# ROB_V1_1.net
KiCad netlist of a schematic drawn in EAGLE
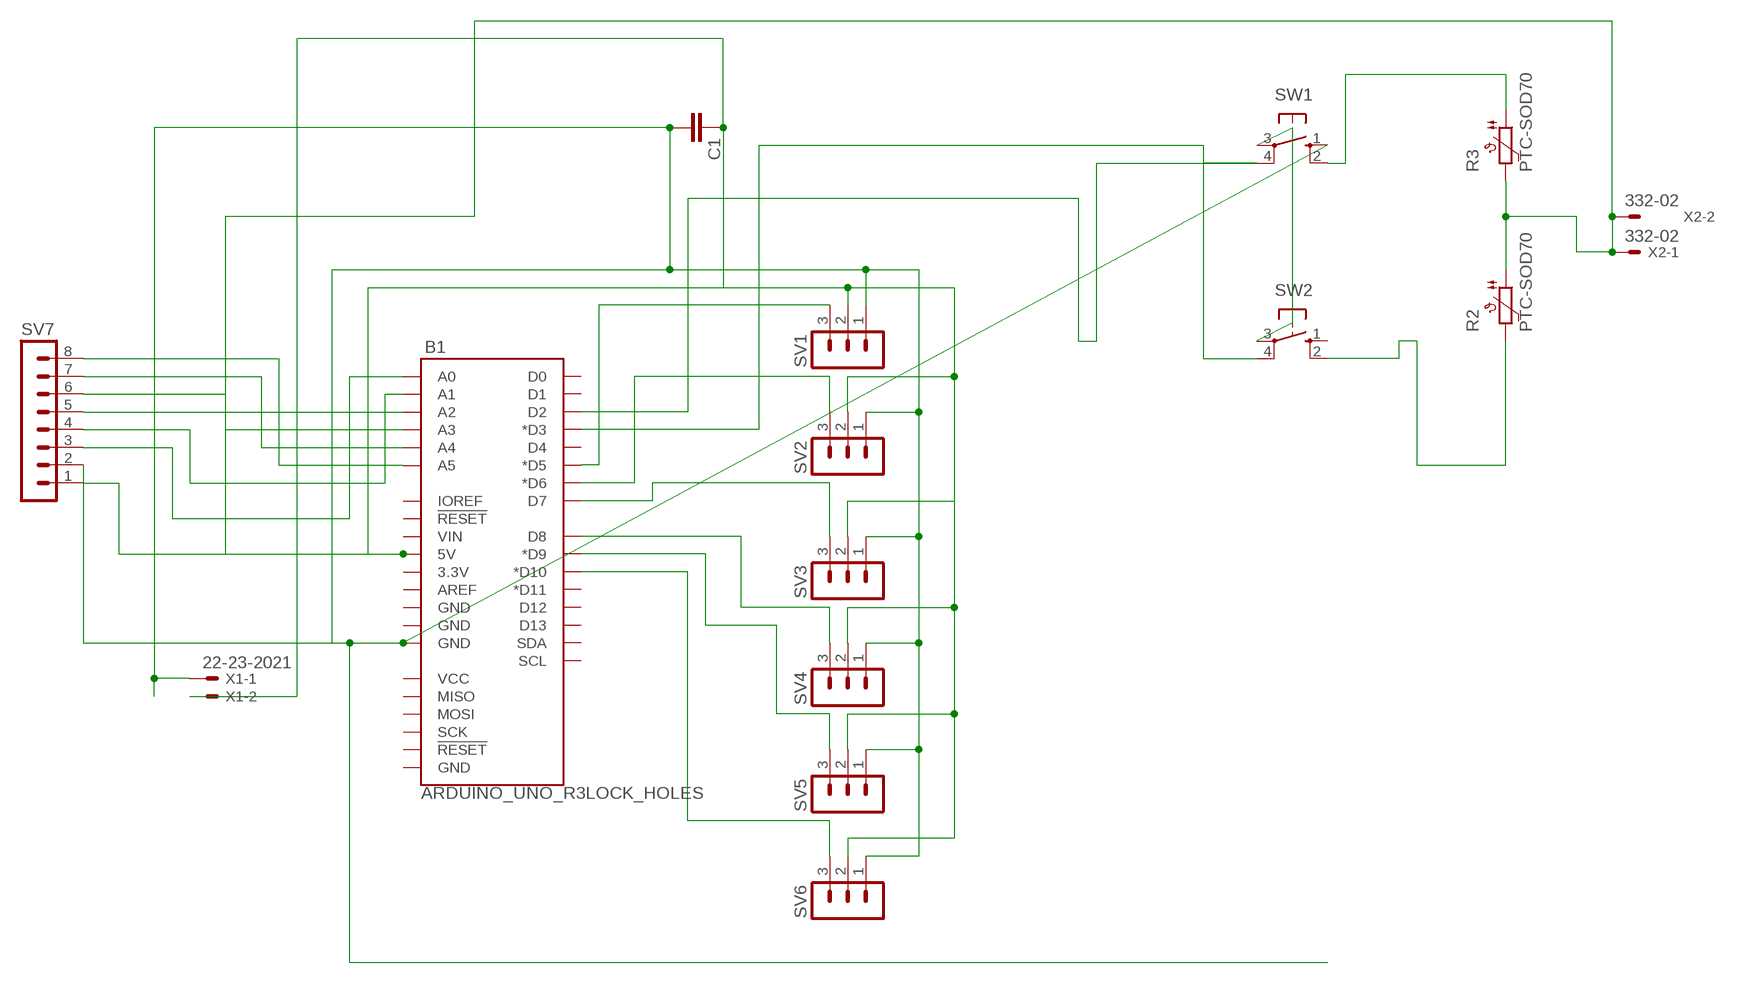
[diagram p0: schematic, sheet 1]

(export (version "E")
  (design (tool "Eeschema 10.0.6"))
  (components
    (comp (ref "B1")
      (value "ARDUINO_UNO_R3LOCK_HOLES")
      (footprint "eagle-import:ARDUINO_R3_LOCK_HOLES")
      (libsource (lib "eagle-import") (part "ARDUINO_UNO_R3LOCK_HOLES"))
    )
    (comp (ref "C1")
      (value "C2.5/2")
      (footprint "eagle-import:C2.5-2")
      (libsource (lib "eagle-import") (part "C2.5/2"))
    )
    (comp (ref "R2")
      (value "PTC-SOD70")
      (footprint "eagle-import:SOD70")
      (libsource (lib "eagle-import") (part "PTC-SOD70"))
    )
    (comp (ref "R3")
      (value "PTC-SOD70")
      (footprint "eagle-import:SOD70")
      (libsource (lib "eagle-import") (part "PTC-SOD70"))
    )
    (comp (ref "SV1")
      (value "MA03-1")
      (footprint "eagle-import:MA03-1")
      (libsource (lib "eagle-import") (part "MA03-1"))
    )
    (comp (ref "SV2")
      (value "MA03-1")
      (footprint "eagle-import:MA03-1")
      (libsource (lib "eagle-import") (part "MA03-1"))
    )
    (comp (ref "SV3")
      (value "MA03-1")
      (footprint "eagle-import:MA03-1")
      (libsource (lib "eagle-import") (part "MA03-1"))
    )
    (comp (ref "SV4")
      (value "MA03-1")
      (footprint "eagle-import:MA03-1")
      (libsource (lib "eagle-import") (part "MA03-1"))
    )
    (comp (ref "SV5")
      (value "MA03-1")
      (footprint "eagle-import:MA03-1")
      (libsource (lib "eagle-import") (part "MA03-1"))
    )
    (comp (ref "SV6")
      (value "MA03-1")
      (footprint "eagle-import:MA03-1")
      (libsource (lib "eagle-import") (part "MA03-1"))
    )
    (comp (ref "SV7")
      (value "MA08-1")
      (footprint "eagle-import:MA08-1")
      (libsource (lib "eagle-import") (part "MA08-1"))
    )
    (comp (ref "SW1")
      (value "10-XX")
      (footprint "eagle-import:B3F-10XX")
      (libsource (lib "eagle-import") (part "10-XX"))
    )
    (comp (ref "SW2")
      (value "10-XX")
      (footprint "eagle-import:B3F-10XX")
      (libsource (lib "eagle-import") (part "10-XX"))
    )
    (comp (ref "X1")
      (value "22-23-2021")
      (footprint "eagle-import:22-23-2021")
      (fields (field (name "MF") "MOLEX"))
      (libsource (lib "eagle-import") (part "22-23-2021"))
    )
    (comp (ref "X2")
      (value "332-02")
      (footprint "eagle-import:332-02")
      (libsource (lib "eagle-import") (part "332-02"))
    )
  )
  (nets
    (net (code "1") (name "Net-(B1-*D3)") (class "Default")
      (node (ref "B1") (pin "D3") (pinfunction "*D3_D3") (pintype "bidirectional"))
      (node (ref "SW2") (pin "4") (pinfunction "P1_4") (pintype "passive"))
    )
    (net (code "2") (name "Net-(B1-*D5)") (class "Default")
      (node (ref "B1") (pin "D5") (pinfunction "*D5_D5") (pintype "bidirectional"))
      (node (ref "SV1") (pin "3") (pinfunction "3_3") (pintype "passive"))
    )
    (net (code "3") (name "Net-(B1-*D6)") (class "Default")
      (node (ref "B1") (pin "D6") (pinfunction "*D6_D6") (pintype "bidirectional"))
      (node (ref "SV2") (pin "3") (pinfunction "3_3") (pintype "passive"))
    )
    (net (code "4") (name "Net-(B1-*D9)") (class "Default")
      (node (ref "B1") (pin "D9") (pinfunction "*D9_D9") (pintype "bidirectional"))
      (node (ref "SV5") (pin "3") (pinfunction "3_3") (pintype "passive"))
    )
    (net (code "5") (name "Net-(B1-*D10)") (class "Default")
      (node (ref "B1") (pin "D10") (pinfunction "*D10_D10") (pintype "bidirectional"))
      (node (ref "SV6") (pin "3") (pinfunction "3_3") (pintype "passive"))
    )
    (net (code "6") (name "Net-(B1-PadA0)") (class "Default")
      (node (ref "B1") (pin "A0") (pinfunction "A0_A0") (pintype "bidirectional"))
      (node (ref "SV7") (pin "3") (pinfunction "3_3") (pintype "passive"))
    )
    (net (code "7") (name "Net-(B1-PadA1)") (class "Default")
      (node (ref "B1") (pin "A1") (pinfunction "A1_A1") (pintype "bidirectional"))
      (node (ref "SV7") (pin "4") (pinfunction "4_4") (pintype "passive"))
    )
    (net (code "8") (name "Net-(B1-PadA2)") (class "Default")
      (node (ref "B1") (pin "A2") (pinfunction "A2_A2") (pintype "bidirectional"))
      (node (ref "SV7") (pin "5") (pinfunction "5_5") (pintype "passive"))
    )
    (net (code "9") (name "Net-(B1-PadA3)") (class "Default")
      (node (ref "B1") (pin "A3") (pinfunction "A3_A3") (pintype "bidirectional"))
      (node (ref "SV7") (pin "6") (pinfunction "6_6") (pintype "passive"))
    )
    (net (code "10") (name "Net-(B1-PadA4)") (class "Default")
      (node (ref "B1") (pin "A4") (pinfunction "A4_A4") (pintype "bidirectional"))
      (node (ref "SV7") (pin "7") (pinfunction "7_7") (pintype "passive"))
    )
    (net (code "11") (name "Net-(B1-PadA5)") (class "Default")
      (node (ref "B1") (pin "A5") (pinfunction "A5_A5") (pintype "bidirectional"))
      (node (ref "SV7") (pin "8") (pinfunction "8_8") (pintype "passive"))
    )
    (net (code "12") (name "Net-(B1-PadD7)") (class "Default")
      (node (ref "B1") (pin "D7") (pinfunction "D7_D7") (pintype "bidirectional"))
      (node (ref "SV3") (pin "3") (pinfunction "3_3") (pintype "passive"))
    )
    (net (code "13") (name "Net-(B1-PadD8)") (class "Default")
      (node (ref "B1") (pin "D8") (pinfunction "D8_D8") (pintype "bidirectional"))
      (node (ref "SV4") (pin "3") (pinfunction "3_3") (pintype "passive"))
    )
    (net (code "14") (name "Net-(SW1-P)") (class "Default")
      (node (ref "SW1") (pin "3") (pinfunction "P_3") (pintype "passive"))
      (node (ref "SW2") (pin "3") (pinfunction "P_3") (pintype "passive"))
    )
    (net (code "15") (name "Net-(SW1-P1)") (class "Default")
      (node (ref "B1") (pin "D2") (pinfunction "D2_D2") (pintype "bidirectional"))
      (node (ref "SW1") (pin "4") (pinfunction "P1_4") (pintype "passive"))
    )
    (net (code "16") (name "Net-(SW1-S)") (class "Default")
      (node (ref "B1") (pin "GND@2") (pinfunction "GND_GND@2") (pintype "bidirectional"))
      (node (ref "C1") (pin "2") (pinfunction "2_2") (pintype "passive"))
      (node (ref "SV1") (pin "1") (pinfunction "1_1") (pintype "passive"))
      (node (ref "SV2") (pin "1") (pinfunction "1_1") (pintype "passive"))
      (node (ref "SV3") (pin "1") (pinfunction "1_1") (pintype "passive"))
      (node (ref "SV4") (pin "1") (pinfunction "1_1") (pintype "passive"))
      (node (ref "SV5") (pin "1") (pinfunction "1_1") (pintype "passive"))
      (node (ref "SV6") (pin "1") (pinfunction "1_1") (pintype "passive"))
      (node (ref "SV7") (pin "2") (pinfunction "2_2") (pintype "passive"))
      (node (ref "SW1") (pin "1") (pinfunction "S_1") (pintype "passive"))
      (node (ref "X1") (pin "1") (pinfunction "S_1") (pintype "passive"))
    )
    (net (code "17") (name "Net-(SW1-S1)") (class "Default")
      (node (ref "R3") (pin "1") (pinfunction "1_1") (pintype "passive"))
      (node (ref "SW1") (pin "2") (pinfunction "S1_2") (pintype "passive"))
    )
    (net (code "18") (name "Net-(SW2-S1)") (class "Default")
      (node (ref "R2") (pin "2") (pinfunction "2_2") (pintype "passive"))
      (node (ref "SW2") (pin "2") (pinfunction "S1_2") (pintype "passive"))
    )
    (net (code "19") (name "Net-(X1B-S)") (class "Default")
      (node (ref "B1") (pin "5V") (pinfunction "5V_5V") (pintype "bidirectional"))
      (node (ref "C1") (pin "1") (pinfunction "1_1") (pintype "passive"))
      (node (ref "R2") (pin "1") (pinfunction "1_1") (pintype "passive"))
      (node (ref "R3") (pin "2") (pinfunction "2_2") (pintype "passive"))
      (node (ref "SV1") (pin "2") (pinfunction "2_2") (pintype "passive"))
      (node (ref "SV2") (pin "2") (pinfunction "2_2") (pintype "passive"))
      (node (ref "SV3") (pin "2") (pinfunction "2_2") (pintype "passive"))
      (node (ref "SV4") (pin "2") (pinfunction "2_2") (pintype "passive"))
      (node (ref "SV5") (pin "2") (pinfunction "2_2") (pintype "passive"))
      (node (ref "SV6") (pin "2") (pinfunction "2_2") (pintype "passive"))
      (node (ref "SV7") (pin "1") (pinfunction "1_1") (pintype "passive"))
      (node (ref "X1") (pin "2") (pinfunction "S_2") (pintype "passive"))
      (node (ref "X2") (pin "1") (pinfunction "S_1") (pintype "passive"))
      (node (ref "X2") (pin "2") (pinfunction "S_2") (pintype "passive"))
    )
    (net (code "20") (name "unconnected-(B1-*D11-PadD11)") (class "Default")
      (node (ref "B1") (pin "D11") (pinfunction "*D11_D11") (pintype "bidirectional"))
    )
    (net (code "21") (name "unconnected-(B1-GND-PadGND@1)") (class "Default")
      (node (ref "B1") (pin "GND@1") (pinfunction "GND_GND@1") (pintype "bidirectional"))
    )
    (net (code "22") (name "unconnected-(B1-GND-PadGND@3)") (class "Default")
      (node (ref "B1") (pin "GND@3") (pinfunction "GND_GND@3") (pintype "bidirectional"))
    )
    (net (code "23") (name "unconnected-(B1-GND-PadGND@4)") (class "Default")
      (node (ref "B1") (pin "GND@4") (pinfunction "GND_GND@4") (pintype "bidirectional"))
    )
    (net (code "24") (name "unconnected-(B1-Pad3.3V)") (class "Default")
      (node (ref "B1") (pin "3.3V") (pinfunction "3.3V_3.3V") (pintype "bidirectional"))
    )
    (net (code "25") (name "unconnected-(B1-PadAREF)") (class "Default")
      (node (ref "B1") (pin "AREF") (pinfunction "AREF_AREF") (pintype "bidirectional"))
    )
    (net (code "26") (name "unconnected-(B1-PadD0)") (class "Default")
      (node (ref "B1") (pin "D0") (pinfunction "D0_D0") (pintype "bidirectional"))
    )
    (net (code "27") (name "unconnected-(B1-PadD1)") (class "Default")
      (node (ref "B1") (pin "D1") (pinfunction "D1_D1") (pintype "bidirectional"))
    )
    (net (code "28") (name "unconnected-(B1-PadD4)") (class "Default")
      (node (ref "B1") (pin "D4") (pinfunction "D4_D4") (pintype "bidirectional"))
    )
    (net (code "29") (name "unconnected-(B1-PadD12)") (class "Default")
      (node (ref "B1") (pin "D12") (pinfunction "D12_D12") (pintype "bidirectional"))
    )
    (net (code "30") (name "unconnected-(B1-PadD13)") (class "Default")
      (node (ref "B1") (pin "D13") (pinfunction "D13_D13") (pintype "bidirectional"))
    )
    (net (code "31") (name "unconnected-(B1-PadIOREF)") (class "Default")
      (node (ref "B1") (pin "IOREF") (pinfunction "IOREF_IOREF") (pintype "bidirectional"))
    )
    (net (code "32") (name "unconnected-(B1-PadMISO)") (class "Default")
      (node (ref "B1") (pin "MISO") (pinfunction "MISO_MISO") (pintype "bidirectional"))
    )
    (net (code "33") (name "unconnected-(B1-PadMOSI)") (class "Default")
      (node (ref "B1") (pin "MOSI") (pinfunction "MOSI_MOSI") (pintype "bidirectional"))
    )
    (net (code "34") (name "unconnected-(B1-PadSCK)") (class "Default")
      (node (ref "B1") (pin "SCK") (pinfunction "SCK_SCK") (pintype "bidirectional"))
    )
    (net (code "35") (name "unconnected-(B1-PadSCL)") (class "Default")
      (node (ref "B1") (pin "SCL") (pinfunction "SCL_SCL") (pintype "bidirectional"))
    )
    (net (code "36") (name "unconnected-(B1-PadSDA)") (class "Default")
      (node (ref "B1") (pin "SDA") (pinfunction "SDA_SDA") (pintype "bidirectional"))
    )
    (net (code "37") (name "unconnected-(B1-PadVCC)") (class "Default")
      (node (ref "B1") (pin "VCC") (pinfunction "VCC_VCC") (pintype "bidirectional"))
    )
    (net (code "38") (name "unconnected-(B1-PadVIN)") (class "Default")
      (node (ref "B1") (pin "VIN") (pinfunction "VIN_VIN") (pintype "bidirectional"))
    )
    (net (code "39") (name "unconnected-(B1-~{RESET}-PadRESET@1)") (class "Default")
      (node (ref "B1") (pin "RESET@1") (pinfunction "~{RESET}_RESET@1") (pintype "bidirectional"))
    )
    (net (code "40") (name "unconnected-(B1-~{RESET}-PadRESET@2)") (class "Default")
      (node (ref "B1") (pin "RESET@2") (pinfunction "~{RESET}_RESET@2") (pintype "bidirectional"))
    )
    (net (code "41") (name "unconnected-(SW2-S-Pad1)") (class "Default")
      (node (ref "SW2") (pin "1") (pinfunction "S_1") (pintype "passive"))
    )
  )
)
